# USB.net
KiCad netlist of a schematic drawn in Altium Designer
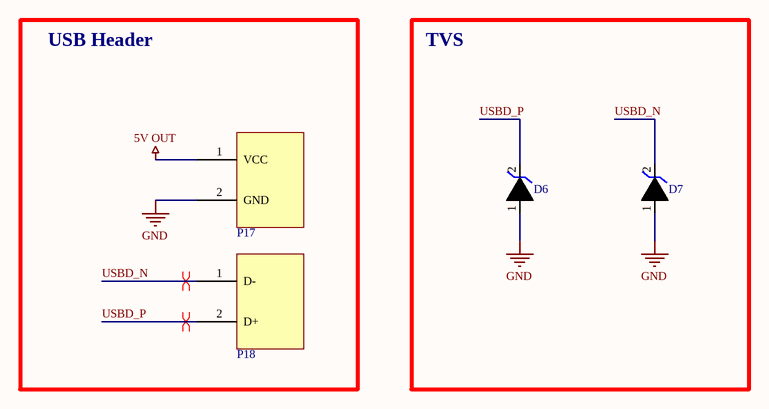
[diagram p0: USB.SchDoc]

(export (version "E")
  (design (tool "Eeschema 10.0.6"))
  (components
    (comp (ref "D6")
      (value "TVS")
      (footprint "0805 TVS DIODE")
      (description "Schematic for TVS diode")
      (libsource (lib "Lib") (part "TVS Diode"))
    )
    (comp (ref "D7")
      (value "TVS")
      (footprint "0805 TVS DIODE")
      (description "Schematic for TVS diode")
      (libsource (lib "Lib") (part "TVS Diode"))
    )
    (comp (ref "P17")
      (value "2-Pin Header")
      (footprint "WR-TBL 322 2H")
      (description "322 series 2 pin header")
      (libsource (lib "Lib") (part "322-2H"))
    )
    (comp (ref "P18")
      (value "2-Pin Header")
      (footprint "WR-TBL 322 2H")
      (description "322 series 2 pin header")
      (libsource (lib "Lib") (part "322-2H"))
    )
  )
  (nets
    (net (code "1") (name "/USBD_N") (class "Default")
      (node (ref "D7") (pin "2") (pinfunction "2_2") (pintype "passive"))
      (node (ref "P18") (pin "1") (pinfunction "VCC_1") (pintype "passive"))
    )
    (net (code "2") (name "/USBD_P") (class "Default")
      (node (ref "D6") (pin "2") (pinfunction "2_2") (pintype "passive"))
      (node (ref "P18") (pin "2") (pinfunction "GND_2") (pintype "passive"))
    )
    (net (code "3") (name "5V OUT") (class "Default")
      (node (ref "P17") (pin "1") (pinfunction "VCC_1") (pintype "passive"))
    )
    (net (code "4") (name "GND") (class "Default")
      (node (ref "D6") (pin "1") (pinfunction "1_1") (pintype "passive"))
      (node (ref "D7") (pin "1") (pinfunction "1_1") (pintype "passive"))
      (node (ref "P17") (pin "2") (pinfunction "GND_2") (pintype "passive"))
    )
  )
)
